# node.net
KiCad netlist of a schematic drawn in EAGLE
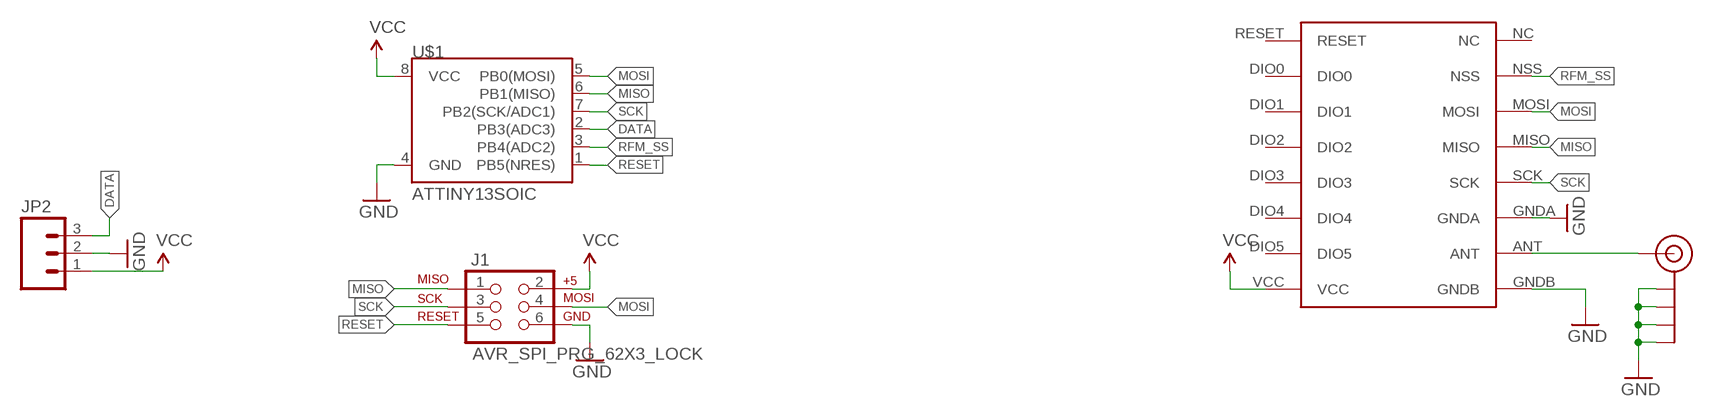
[diagram p0: schematic, sheet 1]

(export (version "E")
  (design (tool "Eeschema 10.0.6"))
  (components
    (comp (ref "J$1")
      (value "SMA_EDGE")
      (footprint "eagle-import:SMA-EDGE")
      (libsource (lib "eagle-import") (part "SMA_EDGE"))
    )
    (comp (ref "J1")
      (value "AVR_SPI_PRG_62X3_LOCK")
      (footprint "eagle-import:2X3_LOCK")
      (libsource (lib "eagle-import") (part "AVR_SPI_PRG_62X3_LOCK"))
    )
    (comp (ref "JP2")
      (value "M03PTH")
      (footprint "eagle-import:1X03")
      (libsource (lib "eagle-import") (part "M03PTH"))
    )
    (comp (ref "U$1")
      (value "ATTINY13SOIC")
      (footprint "eagle-import:SO08")
      (libsource (lib "eagle-import") (part "ATTINY13SOIC"))
    )
    (comp (ref "U$4")
      (value "RFM69HW")
      (footprint "eagle-import:RFM")
      (libsource (lib "eagle-import") (part "RFM69HW"))
    )
  )
  (nets
    (net (code "1") (name "DATA") (class "Default")
      (node (ref "JP2") (pin "3") (pinfunction "3_3") (pintype "passive"))
      (node (ref "U$1") (pin "2") (pinfunction "PB3(ADC3)_2") (pintype "bidirectional"))
    )
    (net (code "2") (name "GND") (class "Default")
      (node (ref "J$1") (pin "GND@0") (pinfunction "GND_GND@0") (pintype "bidirectional"))
      (node (ref "J$1") (pin "GND@1") (pinfunction "GND_GND@1") (pintype "bidirectional"))
      (node (ref "J$1") (pin "GND@2") (pinfunction "GND_GND@2") (pintype "bidirectional"))
      (node (ref "J$1") (pin "GND@3") (pinfunction "GND_GND@3") (pintype "bidirectional"))
      (node (ref "J1") (pin "6") (pinfunction "6_6") (pintype "passive"))
      (node (ref "JP2") (pin "2") (pinfunction "2_2") (pintype "passive"))
      (node (ref "U$1") (pin "4") (pinfunction "GND_4") (pintype "bidirectional"))
      (node (ref "U$4") (pin "GNDA") (pinfunction "GNDA_GNDA") (pintype "bidirectional"))
      (node (ref "U$4") (pin "GNDB") (pinfunction "GNDB_GNDB") (pintype "bidirectional"))
    )
    (net (code "3") (name "MISO") (class "Default")
      (node (ref "J1") (pin "1") (pinfunction "1_1") (pintype "passive"))
      (node (ref "U$1") (pin "6") (pinfunction "PB1(MISO)_6") (pintype "bidirectional"))
      (node (ref "U$4") (pin "MISO") (pinfunction "MISO_MISO") (pintype "bidirectional"))
    )
    (net (code "4") (name "MOSI") (class "Default")
      (node (ref "J1") (pin "4") (pinfunction "4_4") (pintype "passive"))
      (node (ref "U$1") (pin "5") (pinfunction "PB0(MOSI)_5") (pintype "bidirectional"))
      (node (ref "U$4") (pin "MOSI") (pinfunction "MOSI_MOSI") (pintype "bidirectional"))
    )
    (net (code "5") (name "Net-(J$1-SIGNAL)") (class "Default")
      (node (ref "J$1") (pin "SIG") (pinfunction "SIGNAL_SIG") (pintype "bidirectional"))
      (node (ref "U$4") (pin "ANT") (pinfunction "ANT_ANT") (pintype "bidirectional"))
    )
    (net (code "6") (name "RESET") (class "Default")
      (node (ref "J1") (pin "5") (pinfunction "5_5") (pintype "passive"))
      (node (ref "U$1") (pin "1") (pinfunction "PB5(NRES)_1") (pintype "bidirectional"))
    )
    (net (code "7") (name "RFM_SS") (class "Default")
      (node (ref "U$1") (pin "3") (pinfunction "PB4(ADC2)_3") (pintype "bidirectional"))
      (node (ref "U$4") (pin "NSS") (pinfunction "NSS_NSS") (pintype "bidirectional"))
    )
    (net (code "8") (name "SCK") (class "Default")
      (node (ref "J1") (pin "3") (pinfunction "3_3") (pintype "passive"))
      (node (ref "U$1") (pin "7") (pinfunction "PB2(SCK/ADC1)_7") (pintype "bidirectional"))
      (node (ref "U$4") (pin "SCK") (pinfunction "SCK_SCK") (pintype "bidirectional"))
    )
    (net (code "9") (name "VCC") (class "Default")
      (node (ref "J1") (pin "2") (pinfunction "2_2") (pintype "passive"))
      (node (ref "JP2") (pin "1") (pinfunction "1_1") (pintype "passive"))
      (node (ref "U$1") (pin "8") (pinfunction "VCC_8") (pintype "bidirectional"))
      (node (ref "U$4") (pin "VCC") (pinfunction "VCC_VCC") (pintype "bidirectional"))
    )
    (net (code "10") (name "unconnected-(U$4-PadDIO0)") (class "Default")
      (node (ref "U$4") (pin "DIO0") (pinfunction "DIO0_DIO0") (pintype "bidirectional"))
    )
    (net (code "11") (name "unconnected-(U$4-PadDIO1)") (class "Default")
      (node (ref "U$4") (pin "DIO1") (pinfunction "DIO1_DIO1") (pintype "bidirectional"))
    )
    (net (code "12") (name "unconnected-(U$4-PadDIO2)") (class "Default")
      (node (ref "U$4") (pin "DIO2") (pinfunction "DIO2_DIO2") (pintype "bidirectional"))
    )
    (net (code "13") (name "unconnected-(U$4-PadDIO3)") (class "Default")
      (node (ref "U$4") (pin "DIO3") (pinfunction "DIO3_DIO3") (pintype "bidirectional"))
    )
    (net (code "14") (name "unconnected-(U$4-PadDIO4)") (class "Default")
      (node (ref "U$4") (pin "DIO4") (pinfunction "DIO4_DIO4") (pintype "bidirectional"))
    )
    (net (code "15") (name "unconnected-(U$4-PadDIO5)") (class "Default")
      (node (ref "U$4") (pin "DIO5") (pinfunction "DIO5_DIO5") (pintype "bidirectional"))
    )
    (net (code "16") (name "unconnected-(U$4-PadNC)") (class "Default")
      (node (ref "U$4") (pin "NC") (pinfunction "NC_NC") (pintype "bidirectional"))
    )
    (net (code "17") (name "unconnected-(U$4-PadRESET)") (class "Default")
      (node (ref "U$4") (pin "RESET") (pinfunction "RESET_RESET") (pintype "bidirectional"))
    )
  )
)
